# nfc-pn532.net
KiCad netlist of a schematic drawn in EAGLE
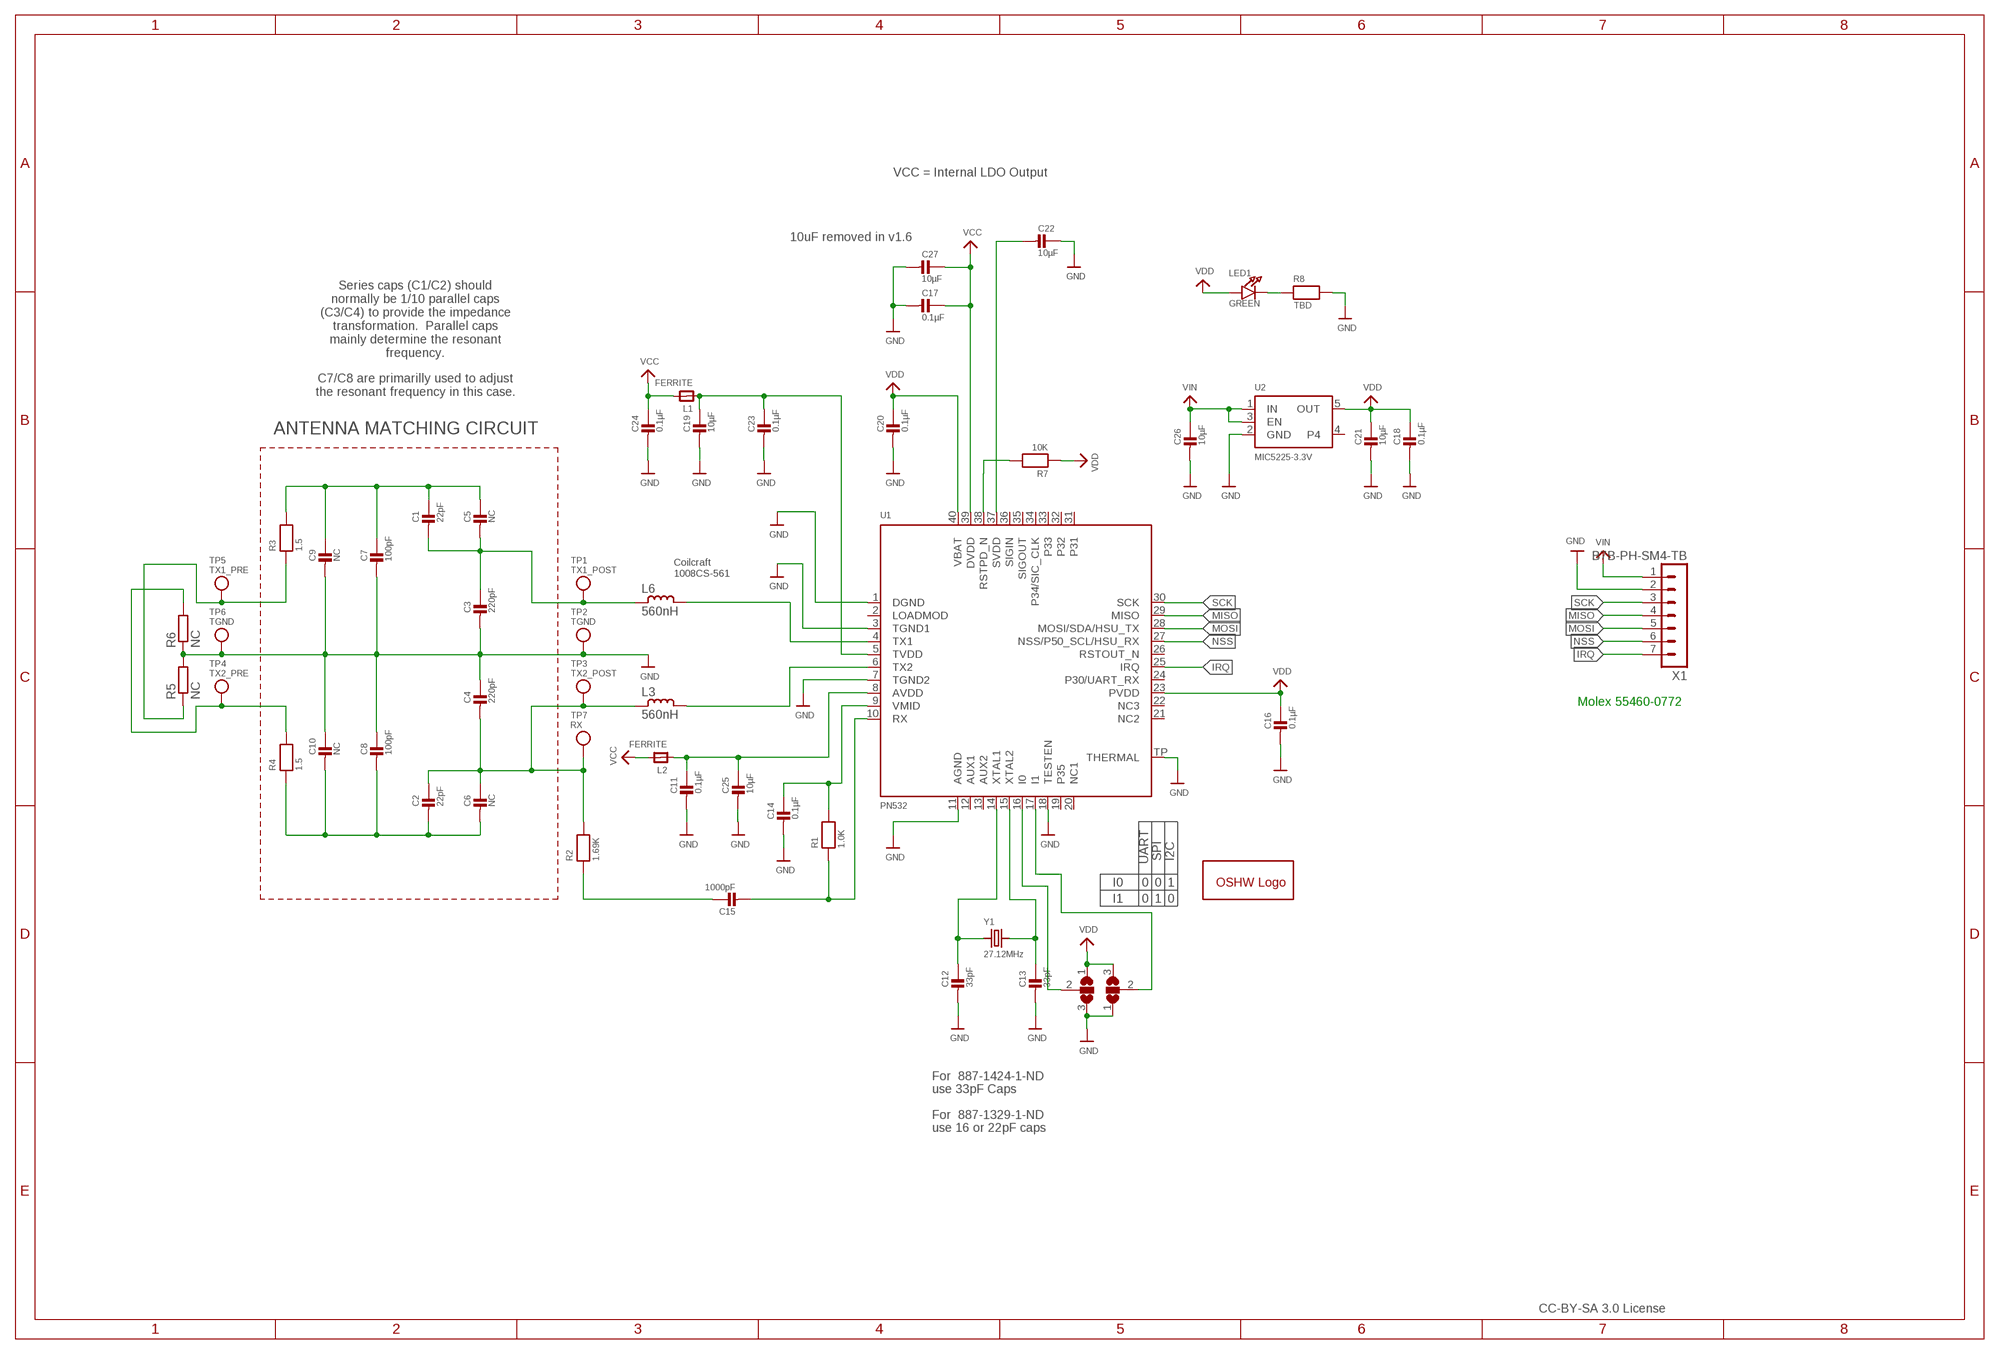
[diagram p0: schematic, sheet 1]

(export (version "E")
  (design (tool "Eeschema 10.0.6"))
  (components
    (comp (ref "C1")
      (value "22pF")
      (footprint "eagle-import:0805-NO")
      (libsource (lib "eagle-import") (part "CAP_CERAMIC0805-NOOUTLINE"))
    )
    (comp (ref "C2")
      (value "22pF")
      (footprint "eagle-import:0805-NO")
      (libsource (lib "eagle-import") (part "CAP_CERAMIC0805-NOOUTLINE"))
    )
    (comp (ref "C3")
      (value "220pF")
      (footprint "eagle-import:0805-NO")
      (libsource (lib "eagle-import") (part "CAP_CERAMIC0805-NOOUTLINE"))
    )
    (comp (ref "C4")
      (value "220pF")
      (footprint "eagle-import:0805-NO")
      (libsource (lib "eagle-import") (part "CAP_CERAMIC0805-NOOUTLINE"))
    )
    (comp (ref "C5")
      (value "NC")
      (footprint "eagle-import:0805-NO")
      (libsource (lib "eagle-import") (part "CAP_CERAMIC0805-NOOUTLINE"))
    )
    (comp (ref "C6")
      (value "NC")
      (footprint "eagle-import:0805-NO")
      (libsource (lib "eagle-import") (part "CAP_CERAMIC0805-NOOUTLINE"))
    )
    (comp (ref "C7")
      (value "100pF")
      (footprint "eagle-import:0805-NO")
      (libsource (lib "eagle-import") (part "CAP_CERAMIC0805-NOOUTLINE"))
    )
    (comp (ref "C8")
      (value "100pF")
      (footprint "eagle-import:0805-NO")
      (libsource (lib "eagle-import") (part "CAP_CERAMIC0805-NOOUTLINE"))
    )
    (comp (ref "C9")
      (value "NC")
      (footprint "eagle-import:0805-NO")
      (libsource (lib "eagle-import") (part "CAP_CERAMIC0805-NOOUTLINE"))
    )
    (comp (ref "C10")
      (value "NC")
      (footprint "eagle-import:0805-NO")
      (libsource (lib "eagle-import") (part "CAP_CERAMIC0805-NOOUTLINE"))
    )
    (comp (ref "C11")
      (value "0.1µF")
      (footprint "eagle-import:0805-NO")
      (libsource (lib "eagle-import") (part "CAP_CERAMIC0805-NOOUTLINE"))
    )
    (comp (ref "C12")
      (value "33pF")
      (footprint "eagle-import:0805-NO")
      (libsource (lib "eagle-import") (part "CAP_CERAMIC0805-NOOUTLINE"))
    )
    (comp (ref "C13")
      (value "33pF")
      (footprint "eagle-import:0805-NO")
      (libsource (lib "eagle-import") (part "CAP_CERAMIC0805-NOOUTLINE"))
    )
    (comp (ref "C14")
      (value "0.1µF")
      (footprint "eagle-import:0805-NO")
      (libsource (lib "eagle-import") (part "CAP_CERAMIC0805-NOOUTLINE"))
    )
    (comp (ref "C15")
      (value "1000pF")
      (footprint "eagle-import:0805-NO")
      (libsource (lib "eagle-import") (part "CAP_CERAMIC0805-NOOUTLINE"))
    )
    (comp (ref "C16")
      (value "0.1µF")
      (footprint "eagle-import:0805-NO")
      (libsource (lib "eagle-import") (part "CAP_CERAMIC0805-NOOUTLINE"))
    )
    (comp (ref "C17")
      (value "0.1µF")
      (footprint "eagle-import:0805-NO")
      (libsource (lib "eagle-import") (part "CAP_CERAMIC0805-NOOUTLINE"))
    )
    (comp (ref "C18")
      (value "0.1µF")
      (footprint "eagle-import:0805-NO")
      (libsource (lib "eagle-import") (part "CAP_CERAMIC0805-NOOUTLINE"))
    )
    (comp (ref "C19")
      (value "10µF")
      (footprint "eagle-import:0805-NO")
      (libsource (lib "eagle-import") (part "CAP_CERAMIC0805-NOOUTLINE"))
    )
    (comp (ref "C20")
      (value "0.1µF")
      (footprint "eagle-import:0805-NO")
      (libsource (lib "eagle-import") (part "CAP_CERAMIC0805-NOOUTLINE"))
    )
    (comp (ref "C21")
      (value "10µF")
      (footprint "eagle-import:0805-NO")
      (libsource (lib "eagle-import") (part "CAP_CERAMIC0805-NOOUTLINE"))
    )
    (comp (ref "C22")
      (value "10µF")
      (footprint "eagle-import:0805-NO")
      (libsource (lib "eagle-import") (part "CAP_CERAMIC0805-NOOUTLINE"))
    )
    (comp (ref "C23")
      (value "0.1µF")
      (footprint "eagle-import:0805-NO")
      (libsource (lib "eagle-import") (part "CAP_CERAMIC0805-NOOUTLINE"))
    )
    (comp (ref "C24")
      (value "0.1µF")
      (footprint "eagle-import:0805-NO")
      (libsource (lib "eagle-import") (part "CAP_CERAMIC0805-NOOUTLINE"))
    )
    (comp (ref "C25")
      (value "10µF")
      (footprint "eagle-import:0805-NO")
      (libsource (lib "eagle-import") (part "CAP_CERAMIC0805-NOOUTLINE"))
    )
    (comp (ref "C26")
      (value "10µF")
      (footprint "eagle-import:0805-NO")
      (libsource (lib "eagle-import") (part "CAP_CERAMIC0805-NOOUTLINE"))
    )
    (comp (ref "C27")
      (value "10µF")
      (footprint "eagle-import:0805-NO")
      (libsource (lib "eagle-import") (part "CAP_CERAMIC0805-NOOUTLINE"))
    )
    (comp (ref "GOLD_ORB_SM1")
      (value "OSHWLOGOLOGO5MM")
      (footprint "eagle-import:OSHW_5MM")
      (libsource (lib "eagle-import") (part "OSHWLOGOLOGO5MM"))
    )
    (comp (ref "L1")
      (value "FERRITE")
      (footprint "eagle-import:0805")
      (libsource (lib "eagle-import") (part "FERRITE0805"))
    )
    (comp (ref "L2")
      (value "FERRITE")
      (footprint "eagle-import:0805")
      (libsource (lib "eagle-import") (part "FERRITE0805"))
    )
    (comp (ref "L3")
      (value "560nH")
      (footprint "eagle-import:L1008CS")
      (libsource (lib "eagle-import") (part "L-1008CS"))
    )
    (comp (ref "L6")
      (value "560nH")
      (footprint "eagle-import:L1008CS")
      (libsource (lib "eagle-import") (part "L-1008CS"))
    )
    (comp (ref "LED1")
      (value "GREEN")
      (footprint "eagle-import:CHIPLED_0805_NOOUTLINE")
      (libsource (lib "eagle-import") (part "LED0805_NOOUTLINE"))
    )
    (comp (ref "R1")
      (value "1.0K")
      (footprint "eagle-import:0805-NO")
      (libsource (lib "eagle-import") (part "RESISTOR0805_NOOUTLINE"))
    )
    (comp (ref "R2")
      (value "1.69K")
      (footprint "eagle-import:0805-NO")
      (libsource (lib "eagle-import") (part "RESISTOR0805_NOOUTLINE"))
    )
    (comp (ref "R3")
      (value "1.5")
      (footprint "eagle-import:0805-NO")
      (libsource (lib "eagle-import") (part "RESISTOR0805_NOOUTLINE"))
    )
    (comp (ref "R4")
      (value "1.5")
      (footprint "eagle-import:0805-NO")
      (libsource (lib "eagle-import") (part "RESISTOR0805_NOOUTLINE"))
    )
    (comp (ref "R5")
      (value "NC")
      (footprint "eagle-import:R0201")
      (libsource (lib "eagle-import") (part "R-EU_R0201"))
    )
    (comp (ref "R6")
      (value "NC")
      (footprint "eagle-import:R0201")
      (libsource (lib "eagle-import") (part "R-EU_R0201"))
    )
    (comp (ref "R7")
      (value "10K")
      (footprint "eagle-import:0805-NO")
      (libsource (lib "eagle-import") (part "RESISTOR0805_NOOUTLINE"))
    )
    (comp (ref "R8")
      (value "TBD")
      (footprint "eagle-import:0805-NO")
      (libsource (lib "eagle-import") (part "RESISTOR0805_NOOUTLINE"))
    )
    (comp (ref "SJ1")
      (value "SJ2W")
      (footprint "eagle-import:SJ_2")
      (libsource (lib "eagle-import") (part "SJ2W"))
    )
    (comp (ref "SJ2")
      (value "SJ2W")
      (footprint "eagle-import:SJ_2")
      (libsource (lib "eagle-import") (part "SJ2W"))
    )
    (comp (ref "TP1")
      (value "TX1_POST")
      (footprint "eagle-import:TESTPOINT_ROUND_1MM")
      (libsource (lib "eagle-import") (part "TESTPOINTROUND1MM"))
    )
    (comp (ref "TP2")
      (value "TGND")
      (footprint "eagle-import:TESTPOINT_ROUND_1MM")
      (libsource (lib "eagle-import") (part "TESTPOINTROUND1MM"))
    )
    (comp (ref "TP3")
      (value "TX2_POST")
      (footprint "eagle-import:TESTPOINT_ROUND_1MM")
      (libsource (lib "eagle-import") (part "TESTPOINTROUND1MM"))
    )
    (comp (ref "TP4")
      (value "TX2_PRE")
      (footprint "eagle-import:TESTPOINT_ROUND_1MM")
      (libsource (lib "eagle-import") (part "TESTPOINTROUND1MM"))
    )
    (comp (ref "TP5")
      (value "TX1_PRE")
      (footprint "eagle-import:TESTPOINT_ROUND_1MM")
      (libsource (lib "eagle-import") (part "TESTPOINTROUND1MM"))
    )
    (comp (ref "TP6")
      (value "TGND")
      (footprint "eagle-import:TESTPOINT_ROUND_1MM")
      (libsource (lib "eagle-import") (part "TESTPOINTROUND1MM"))
    )
    (comp (ref "TP7")
      (value "RX")
      (footprint "eagle-import:TESTPOINT_ROUND_1MM")
      (libsource (lib "eagle-import") (part "TESTPOINTROUND1MM"))
    )
    (comp (ref "U1")
      (value "PN532")
      (footprint "eagle-import:HVQFN40-6X6")
      (libsource (lib "eagle-import") (part "PN532"))
    )
    (comp (ref "U2")
      (value "MIC5225-3.3V")
      (footprint "eagle-import:SOT23-5")
      (libsource (lib "eagle-import") (part "VREG_SOT23-5"))
    )
    (comp (ref "X1")
      (value "B7B-PH-SM4-TB")
      (footprint "eagle-import:B7B-PH-SM4-TB")
      (libsource (lib "eagle-import") (part "B7B-PH-SM4-TB"))
    )
    (comp (ref "Y1")
      (value "27.12MHz")
      (footprint "eagle-import:CRYSTAL_3.2X2.5")
      (libsource (lib "eagle-import") (part "CRYSTAL3.2X2.5"))
    )
  )
  (nets
    (net (code "1") (name "GND") (class "Default")
      (node (ref "C10") (pin "1") (pinfunction "1_1") (pintype "passive"))
      (node (ref "C11") (pin "2") (pinfunction "2_2") (pintype "passive"))
      (node (ref "C12") (pin "2") (pinfunction "2_2") (pintype "passive"))
      (node (ref "C13") (pin "2") (pinfunction "2_2") (pintype "passive"))
      (node (ref "C14") (pin "2") (pinfunction "2_2") (pintype "passive"))
      (node (ref "C16") (pin "2") (pinfunction "2_2") (pintype "passive"))
      (node (ref "C17") (pin "2") (pinfunction "2_2") (pintype "passive"))
      (node (ref "C18") (pin "2") (pinfunction "2_2") (pintype "passive"))
      (node (ref "C19") (pin "2") (pinfunction "2_2") (pintype "passive"))
      (node (ref "C20") (pin "2") (pinfunction "2_2") (pintype "passive"))
      (node (ref "C21") (pin "2") (pinfunction "2_2") (pintype "passive"))
      (node (ref "C22") (pin "1") (pinfunction "1_1") (pintype "passive"))
      (node (ref "C23") (pin "2") (pinfunction "2_2") (pintype "passive"))
      (node (ref "C24") (pin "2") (pinfunction "2_2") (pintype "passive"))
      (node (ref "C25") (pin "2") (pinfunction "2_2") (pintype "passive"))
      (node (ref "C26") (pin "2") (pinfunction "2_2") (pintype "passive"))
      (node (ref "C27") (pin "2") (pinfunction "2_2") (pintype "passive"))
      (node (ref "C3") (pin "2") (pinfunction "2_2") (pintype "passive"))
      (node (ref "C4") (pin "1") (pinfunction "1_1") (pintype "passive"))
      (node (ref "C7") (pin "2") (pinfunction "2_2") (pintype "passive"))
      (node (ref "C8") (pin "1") (pinfunction "1_1") (pintype "passive"))
      (node (ref "C9") (pin "2") (pinfunction "2_2") (pintype "passive"))
      (node (ref "R5") (pin "2") (pinfunction "2_2") (pintype "passive"))
      (node (ref "R6") (pin "1") (pinfunction "1_1") (pintype "passive"))
      (node (ref "R8") (pin "2") (pinfunction "2_2") (pintype "passive"))
      (node (ref "SJ1") (pin "3") (pinfunction "3_3") (pintype "passive"))
      (node (ref "SJ2") (pin "1") (pinfunction "1_1") (pintype "passive"))
      (node (ref "TP2") (pin "P$1") (pinfunction "P$1_P$1") (pintype "bidirectional"))
      (node (ref "TP6") (pin "P$1") (pinfunction "P$1_P$1") (pintype "bidirectional"))
      (node (ref "U1") (pin "1") (pinfunction "DGND_1") (pintype "bidirectional"))
      (node (ref "U1") (pin "11") (pinfunction "AGND_11") (pintype "bidirectional"))
      (node (ref "U1") (pin "18") (pinfunction "TESTEN_18") (pintype "bidirectional"))
      (node (ref "U1") (pin "3") (pinfunction "TGND1_3") (pintype "bidirectional"))
      (node (ref "U1") (pin "7") (pinfunction "TGND2_7") (pintype "bidirectional"))
      (node (ref "U1") (pin "TP") (pinfunction "THERMAL_TP") (pintype "bidirectional"))
      (node (ref "U2") (pin "2") (pinfunction "GND_2") (pintype "power_in"))
      (node (ref "X1") (pin "2") (pinfunction "2_2") (pintype "passive"))
    )
    (net (code "2") (name "IRQ") (class "Default")
      (node (ref "U1") (pin "25") (pinfunction "IRQ_25") (pintype "bidirectional"))
      (node (ref "X1") (pin "7") (pinfunction "7_7") (pintype "passive"))
    )
    (net (code "3") (name "MISO") (class "Default")
      (node (ref "U1") (pin "29") (pinfunction "MISO_29") (pintype "bidirectional"))
      (node (ref "X1") (pin "4") (pinfunction "4_4") (pintype "passive"))
    )
    (net (code "4") (name "MOSI") (class "Default")
      (node (ref "U1") (pin "28") (pinfunction "MOSI/SDA/HSU_TX_28") (pintype "bidirectional"))
      (node (ref "X1") (pin "5") (pinfunction "5_5") (pintype "passive"))
    )
    (net (code "5") (name "NSS") (class "Default")
      (node (ref "U1") (pin "27") (pinfunction "NSS/P50_SCL/HSU_RX_27") (pintype "bidirectional"))
      (node (ref "X1") (pin "6") (pinfunction "6_6") (pintype "passive"))
    )
    (net (code "6") (name "Net-(C1-Pad1)") (class "Default")
      (node (ref "C1") (pin "1") (pinfunction "1_1") (pintype "passive"))
      (node (ref "C5") (pin "1") (pinfunction "1_1") (pintype "passive"))
      (node (ref "C7") (pin "1") (pinfunction "1_1") (pintype "passive"))
      (node (ref "C9") (pin "1") (pinfunction "1_1") (pintype "passive"))
      (node (ref "R3") (pin "2") (pinfunction "2_2") (pintype "passive"))
    )
    (net (code "7") (name "Net-(C10-Pad2)") (class "Default")
      (node (ref "C10") (pin "2") (pinfunction "2_2") (pintype "passive"))
      (node (ref "C2") (pin "2") (pinfunction "2_2") (pintype "passive"))
      (node (ref "C6") (pin "2") (pinfunction "2_2") (pintype "passive"))
      (node (ref "C8") (pin "2") (pinfunction "2_2") (pintype "passive"))
      (node (ref "R4") (pin "1") (pinfunction "1_1") (pintype "passive"))
    )
    (net (code "8") (name "Net-(C15-Pad1)") (class "Default")
      (node (ref "C15") (pin "1") (pinfunction "1_1") (pintype "passive"))
      (node (ref "R2") (pin "1") (pinfunction "1_1") (pintype "passive"))
    )
    (net (code "9") (name "Net-(L1-P$1)") (class "Default")
      (node (ref "C19") (pin "1") (pinfunction "1_1") (pintype "passive"))
      (node (ref "C23") (pin "1") (pinfunction "1_1") (pintype "passive"))
      (node (ref "L1") (pin "1") (pinfunction "P$1_1") (pintype "passive"))
      (node (ref "U1") (pin "5") (pinfunction "TVDD_5") (pintype "bidirectional"))
    )
    (net (code "10") (name "Net-(L2-P$1)") (class "Default")
      (node (ref "C11") (pin "1") (pinfunction "1_1") (pintype "passive"))
      (node (ref "C25") (pin "1") (pinfunction "1_1") (pintype "passive"))
      (node (ref "L2") (pin "1") (pinfunction "P$1_1") (pintype "passive"))
      (node (ref "U1") (pin "8") (pinfunction "AVDD_8") (pintype "bidirectional"))
    )
    (net (code "11") (name "Net-(L3-P$1)") (class "Default")
      (node (ref "C2") (pin "1") (pinfunction "1_1") (pintype "passive"))
      (node (ref "C4") (pin "2") (pinfunction "2_2") (pintype "passive"))
      (node (ref "C6") (pin "1") (pinfunction "1_1") (pintype "passive"))
      (node (ref "L3") (pin "1") (pinfunction "P$1_1") (pintype "passive"))
      (node (ref "R2") (pin "2") (pinfunction "2_2") (pintype "passive"))
      (node (ref "TP3") (pin "P$1") (pinfunction "P$1_P$1") (pintype "bidirectional"))
      (node (ref "TP7") (pin "P$1") (pinfunction "P$1_P$1") (pintype "bidirectional"))
    )
    (net (code "12") (name "Net-(L3-P$2)") (class "Default")
      (node (ref "L3") (pin "2") (pinfunction "P$2_2") (pintype "passive"))
      (node (ref "U1") (pin "6") (pinfunction "TX2_6") (pintype "bidirectional"))
    )
    (net (code "13") (name "Net-(L6-P$1)") (class "Default")
      (node (ref "C1") (pin "2") (pinfunction "2_2") (pintype "passive"))
      (node (ref "C3") (pin "1") (pinfunction "1_1") (pintype "passive"))
      (node (ref "C5") (pin "2") (pinfunction "2_2") (pintype "passive"))
      (node (ref "L6") (pin "1") (pinfunction "P$1_1") (pintype "passive"))
      (node (ref "TP1") (pin "P$1") (pinfunction "P$1_P$1") (pintype "bidirectional"))
    )
    (net (code "14") (name "Net-(L6-P$2)") (class "Default")
      (node (ref "L6") (pin "2") (pinfunction "P$2_2") (pintype "passive"))
      (node (ref "U1") (pin "4") (pinfunction "TX1_4") (pintype "bidirectional"))
    )
    (net (code "15") (name "Net-(LED1-PadC)") (class "Default")
      (node (ref "LED1") (pin "C") (pinfunction "C_C") (pintype "passive"))
      (node (ref "R8") (pin "1") (pinfunction "1_1") (pintype "passive"))
    )
    (net (code "16") (name "Net-(R3-Pad1)") (class "Default")
      (node (ref "R3") (pin "1") (pinfunction "1_1") (pintype "passive"))
      (node (ref "R5") (pin "1") (pinfunction "1_1") (pintype "passive"))
      (node (ref "TP5") (pin "P$1") (pinfunction "P$1_P$1") (pintype "bidirectional"))
    )
    (net (code "17") (name "Net-(R4-Pad2)") (class "Default")
      (node (ref "R4") (pin "2") (pinfunction "2_2") (pintype "passive"))
      (node (ref "R6") (pin "2") (pinfunction "2_2") (pintype "passive"))
      (node (ref "TP4") (pin "P$1") (pinfunction "P$1_P$1") (pintype "bidirectional"))
    )
    (net (code "18") (name "Net-(U1-I0)") (class "Default")
      (node (ref "SJ1") (pin "2") (pinfunction "2_2") (pintype "passive"))
      (node (ref "U1") (pin "16") (pinfunction "I0_16") (pintype "bidirectional"))
    )
    (net (code "19") (name "Net-(U1-I1)") (class "Default")
      (node (ref "SJ2") (pin "2") (pinfunction "2_2") (pintype "passive"))
      (node (ref "U1") (pin "17") (pinfunction "I1_17") (pintype "bidirectional"))
    )
    (net (code "20") (name "Net-(U1-RSTPD_N)") (class "Default")
      (node (ref "R7") (pin "2") (pinfunction "2_2") (pintype "passive"))
      (node (ref "U1") (pin "38") (pinfunction "RSTPD_N_38") (pintype "bidirectional"))
    )
    (net (code "21") (name "Net-(U1-RX)") (class "Default")
      (node (ref "C15") (pin "2") (pinfunction "2_2") (pintype "passive"))
      (node (ref "R1") (pin "1") (pinfunction "1_1") (pintype "passive"))
      (node (ref "U1") (pin "10") (pinfunction "RX_10") (pintype "bidirectional"))
    )
    (net (code "22") (name "Net-(U1-SVDD)") (class "Default")
      (node (ref "C22") (pin "2") (pinfunction "2_2") (pintype "passive"))
      (node (ref "U1") (pin "37") (pinfunction "SVDD_37") (pintype "bidirectional"))
    )
    (net (code "23") (name "Net-(U1-VMID)") (class "Default")
      (node (ref "C14") (pin "1") (pinfunction "1_1") (pintype "passive"))
      (node (ref "R1") (pin "2") (pinfunction "2_2") (pintype "passive"))
      (node (ref "U1") (pin "9") (pinfunction "VMID_9") (pintype "bidirectional"))
    )
    (net (code "24") (name "Net-(U1-XTAL1)") (class "Default")
      (node (ref "C12") (pin "1") (pinfunction "1_1") (pintype "passive"))
      (node (ref "U1") (pin "14") (pinfunction "XTAL1_14") (pintype "bidirectional"))
      (node (ref "Y1") (pin "1") (pinfunction "1_1") (pintype "passive"))
    )
    (net (code "25") (name "Net-(U1-XTAL2)") (class "Default")
      (node (ref "C13") (pin "1") (pinfunction "1_1") (pintype "passive"))
      (node (ref "U1") (pin "15") (pinfunction "XTAL2_15") (pintype "bidirectional"))
      (node (ref "Y1") (pin "2") (pinfunction "2_2") (pintype "passive"))
    )
    (net (code "26") (name "SCK") (class "Default")
      (node (ref "U1") (pin "30") (pinfunction "SCK_30") (pintype "bidirectional"))
      (node (ref "X1") (pin "3") (pinfunction "3_3") (pintype "passive"))
    )
    (net (code "27") (name "VCC") (class "Default")
      (node (ref "C17") (pin "1") (pinfunction "1_1") (pintype "passive"))
      (node (ref "C24") (pin "1") (pinfunction "1_1") (pintype "passive"))
      (node (ref "C27") (pin "1") (pinfunction "1_1") (pintype "passive"))
      (node (ref "L1") (pin "2") (pinfunction "P$2_2") (pintype "passive"))
      (node (ref "L2") (pin "2") (pinfunction "P$2_2") (pintype "passive"))
      (node (ref "U1") (pin "39") (pinfunction "DVDD_39") (pintype "bidirectional"))
    )
    (net (code "28") (name "VDD") (class "Default")
      (node (ref "C16") (pin "1") (pinfunction "1_1") (pintype "passive"))
      (node (ref "C18") (pin "1") (pinfunction "1_1") (pintype "passive"))
      (node (ref "C20") (pin "1") (pinfunction "1_1") (pintype "passive"))
      (node (ref "C21") (pin "1") (pinfunction "1_1") (pintype "passive"))
      (node (ref "LED1") (pin "A") (pinfunction "A_A") (pintype "passive"))
      (node (ref "R7") (pin "1") (pinfunction "1_1") (pintype "passive"))
      (node (ref "SJ1") (pin "1") (pinfunction "1_1") (pintype "passive"))
      (node (ref "SJ2") (pin "3") (pinfunction "3_3") (pintype "passive"))
      (node (ref "U1") (pin "23") (pinfunction "PVDD_23") (pintype "bidirectional"))
      (node (ref "U1") (pin "40") (pinfunction "VBAT_40") (pintype "bidirectional"))
      (node (ref "U2") (pin "5") (pinfunction "OUT_5") (pintype "power_in"))
    )
    (net (code "29") (name "VIN") (class "Default")
      (node (ref "C26") (pin "1") (pinfunction "1_1") (pintype "passive"))
      (node (ref "U2") (pin "1") (pinfunction "IN_1") (pintype "power_in"))
      (node (ref "U2") (pin "3") (pinfunction "EN_3") (pintype "input"))
      (node (ref "X1") (pin "1") (pinfunction "1_1") (pintype "passive"))
    )
    (net (code "30") (name "unconnected-(U1-AUX1-Pad12)") (class "Default")
      (node (ref "U1") (pin "12") (pinfunction "AUX1_12") (pintype "bidirectional"))
    )
    (net (code "31") (name "unconnected-(U1-AUX2-Pad13)") (class "Default")
      (node (ref "U1") (pin "13") (pinfunction "AUX2_13") (pintype "bidirectional"))
    )
    (net (code "32") (name "unconnected-(U1-LOADMOD-Pad2)") (class "Default")
      (node (ref "U1") (pin "2") (pinfunction "LOADMOD_2") (pintype "bidirectional"))
    )
    (net (code "33") (name "unconnected-(U1-NC1-Pad20)") (class "Default")
      (node (ref "U1") (pin "20") (pinfunction "NC1_20") (pintype "bidirectional"))
    )
    (net (code "34") (name "unconnected-(U1-NC2-Pad21)") (class "Default")
      (node (ref "U1") (pin "21") (pinfunction "NC2_21") (pintype "bidirectional"))
    )
    (net (code "35") (name "unconnected-(U1-NC3-Pad22)") (class "Default")
      (node (ref "U1") (pin "22") (pinfunction "NC3_22") (pintype "bidirectional"))
    )
    (net (code "36") (name "unconnected-(U1-P30{slash}UART_RX-Pad24)") (class "Default")
      (node (ref "U1") (pin "24") (pinfunction "P30/UART_RX_24") (pintype "bidirectional"))
    )
    (net (code "37") (name "unconnected-(U1-P31-Pad31)") (class "Default")
      (node (ref "U1") (pin "31") (pinfunction "P31_31") (pintype "bidirectional"))
    )
    (net (code "38") (name "unconnected-(U1-P32-Pad32)") (class "Default")
      (node (ref "U1") (pin "32") (pinfunction "P32_32") (pintype "bidirectional"))
    )
    (net (code "39") (name "unconnected-(U1-P33-Pad33)") (class "Default")
      (node (ref "U1") (pin "33") (pinfunction "P33_33") (pintype "bidirectional"))
    )
    (net (code "40") (name "unconnected-(U1-P34{slash}SIC_CLK-Pad34)") (class "Default")
      (node (ref "U1") (pin "34") (pinfunction "P34/SIC_CLK_34") (pintype "bidirectional"))
    )
    (net (code "41") (name "unconnected-(U1-P35-Pad19)") (class "Default")
      (node (ref "U1") (pin "19") (pinfunction "P35_19") (pintype "bidirectional"))
    )
    (net (code "42") (name "unconnected-(U1-RSTOUT_N-Pad26)") (class "Default")
      (node (ref "U1") (pin "26") (pinfunction "RSTOUT_N_26") (pintype "bidirectional"))
    )
    (net (code "43") (name "unconnected-(U1-SIGIN-Pad36)") (class "Default")
      (node (ref "U1") (pin "36") (pinfunction "SIGIN_36") (pintype "bidirectional"))
    )
    (net (code "44") (name "unconnected-(U1-SIGOUT-Pad35)") (class "Default")
      (node (ref "U1") (pin "35") (pinfunction "SIGOUT_35") (pintype "bidirectional"))
    )
    (net (code "45") (name "unconnected-(U2-P4-Pad4)") (class "Default")
      (node (ref "U2") (pin "4") (pinfunction "P4_4") (pintype "bidirectional"))
    )
  )
)
